# Main.net
KiCad netlist of a schematic drawn in Altium Designer
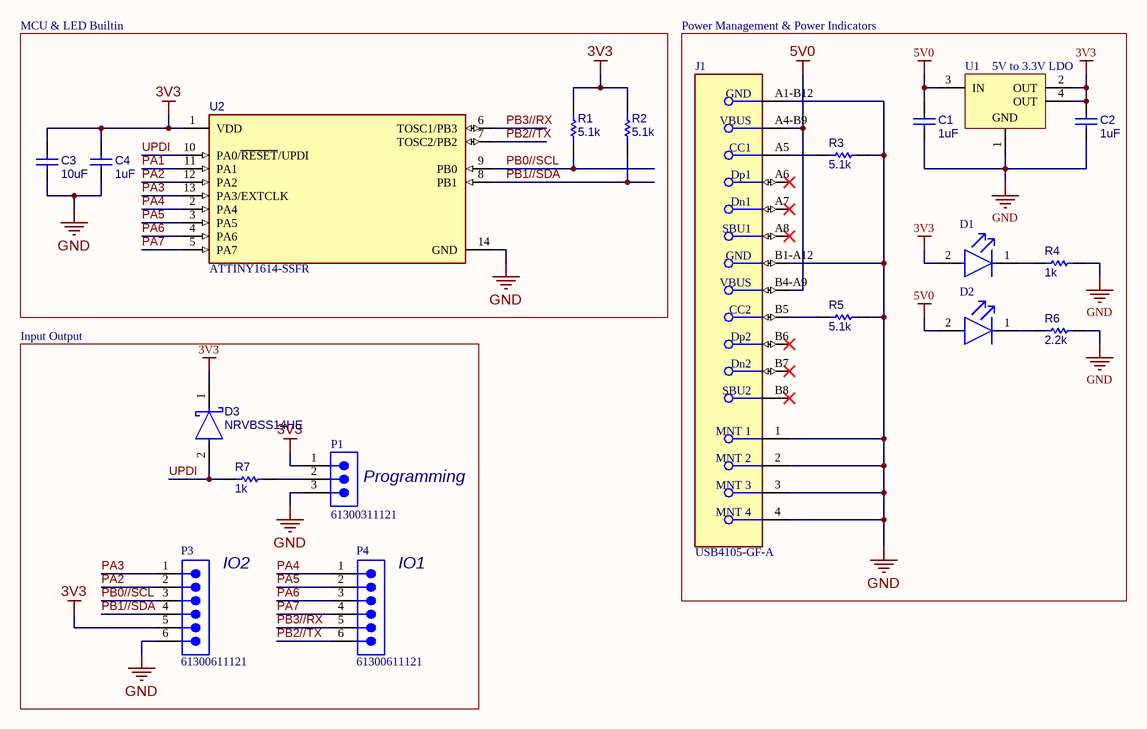
[diagram p0: Main.SchDoc]

(export (version "E")
  (design (tool "Eeschema 10.0.6"))
  (components
    (comp (ref "C1")
      (value "1uF")
      (footprint "WCAP-CSGP_0603_L1.6W0.8H0.8_Reflow")
      (description "10V tolerance")
      (libsource (lib "Altium Content Vault") (part "Capacitor_Non-Polarized"))
    )
    (comp (ref "C2")
      (value "1uF")
      (footprint "WCAP-CSGP_0603_L1.6W0.8H0.8_Reflow")
      (description "10V tolerance")
      (libsource (lib "Altium Content Vault") (part "Capacitor_Non-Polarized"))
    )
    (comp (ref "C3")
      (value "10uF")
      (footprint "WCAP-CSGP_0603_L1.6W0.8H0.8_Reflow")
      (description "10V tolerance")
      (libsource (lib "Altium Content Vault") (part "Capacitor_Non-Polarized"))
    )
    (comp (ref "C4")
      (value "1uF")
      (footprint "WCAP-CSGP_0603_L1.6W0.8H0.8_Reflow")
      (description "10V tolerance")
      (libsource (lib "Altium Content Vault") (part "Capacitor_Non-Polarized"))
    )
    (comp (ref "D1")
      (value "LTST-C190KGKT")
      (footprint "FP-LTST-C190KGKT-MFG")
      (description "LED GREEN CLEAR CHIP SMD")
      (libsource (lib "Altium Content Vault") (part "8706943c75ba83719d021d2fdc84c58"))
    )
    (comp (ref "D2")
      (value "LTST-C190KGKT")
      (footprint "FP-LTST-C190KGKT-MFG")
      (description "LED GREEN CLEAR CHIP SMD")
      (libsource (lib "Altium Content Vault") (part "8706943c75ba83719d021d2fdc84c58"))
    )
    (comp (ref "D3")
      (value "NRVBSS14HE")
      (footprint "FP-477AD-MFG")
      (description "NRVBSS14HE Rectifier Diode, Schottky, 1 Phase, 1 Element, 1A, 40V V(RRM), Silicon")
      (libsource (lib "Altium Content Vault") (part "c1678fac7984e62e0809fbf79c06691"))
    )
    (comp (ref "J1")
      (value "USB4105-GF-A")
      (footprint "FP-USB4105-GF-A-MFG")
      (description "CONN RCPT USB2.0 TYPEC 5A")
      (fields
        (field (name "MANUFACTURER") "GCT")
        (field (name "OCTOPART") "https://octopart.com/usb4105-gf-a-gct-106627878")
      )
      (libsource (lib "Altium Content Vault") (part "e7c17a616881a82b79941196b4bec10"))
    )
    (comp (ref "P1")
      (value "61300311121")
      (footprint "61300311121")
      (description "THT Vertical Pin Header WR-PHD, Pitch 2.54 mm, Single Row, 3 pins")
      (libsource (lib "Altium Content Vault") (part "Header_Male_1R_03P"))
    )
    (comp (ref "P3")
      (value "61300611121")
      (footprint "61300611121")
      (libsource (lib "Altium Content Vault") (part "Header_Male_1R_06P"))
    )
    (comp (ref "P4")
      (value "61300611121")
      (footprint "61300611121")
      (libsource (lib "Altium Content Vault") (part "Header_Male_1R_06P"))
    )
    (comp (ref "R1")
      (value "5.1k")
      (footprint "RESC1608X55X25NL10T15")
      (libsource (lib "Altium Content Vault") (part "RES"))
    )
    (comp (ref "R2")
      (value "5.1k")
      (footprint "RESC1608X55X25NL10T15")
      (libsource (lib "Altium Content Vault") (part "RES"))
    )
    (comp (ref "R3")
      (value "5.1k")
      (footprint "RESC1608X55X25NL10T15")
      (libsource (lib "Altium Content Vault") (part "RES"))
    )
    (comp (ref "R4")
      (value "1k")
      (footprint "RESC1608X55X25NL10T15")
      (libsource (lib "Altium Content Vault") (part "RES"))
    )
    (comp (ref "R5")
      (value "5.1k")
      (footprint "RESC1608X55X25NL10T15")
      (libsource (lib "Altium Content Vault") (part "RES"))
    )
    (comp (ref "R6")
      (value "2.2k")
      (footprint "RESC1608X55X25NL10T15")
      (libsource (lib "Altium Content Vault") (part "RES"))
    )
    (comp (ref "R7")
      (value "1k")
      (footprint "RESC1608X55X25NL10T15")
      (libsource (lib "Altium Content Vault") (part "RES"))
    )
    (comp (ref "U1")
      (value "TLV1117LV33DCYR")
      (footprint "DCY0004A_N")
      (fields (field (name "MANUFACTURER") "Texas Instruments"))
      (libsource (lib "Altium Content Vault") (part "TI-TLV1117LV33DCY4"))
    )
    (comp (ref "U2")
      (value "ATTINY1614-SSFR")
      (footprint "FP-C04-065-D3X-MFG")
      (description "IC MCU 8BIT 16KB FLASH 14SOIC")
      (fields
        (field (name "MANUFACTURER") "Microchip")
        (field (name "OCTOPART") "https://octopart.com/attiny1614-ssfr-microchip-82181131")
      )
      (libsource (lib "Altium Content Vault") (part "72c199063961b341655dca604db29b7"))
    )
  )
  (nets
    (net (code "1") (name "/PA1") (class "Default")
      (node (ref "U2") (pin "11") (pinfunction "PA1_11") (pintype "input"))
    )
    (net (code "2") (name "/PA2") (class "Default")
      (node (ref "P3") (pin "2") (pinfunction "2_2") (pintype "passive"))
      (node (ref "U2") (pin "12") (pinfunction "PA2_12") (pintype "input"))
    )
    (net (code "3") (name "/PA3") (class "Default")
      (node (ref "P3") (pin "1") (pinfunction "1_1") (pintype "passive"))
      (node (ref "U2") (pin "13") (pinfunction "PA3/EXTCLK_13") (pintype "input"))
    )
    (net (code "4") (name "/PA4") (class "Default")
      (node (ref "P4") (pin "1") (pinfunction "1_1") (pintype "passive"))
      (node (ref "U2") (pin "2") (pinfunction "PA4_2") (pintype "input"))
    )
    (net (code "5") (name "/PA5") (class "Default")
      (node (ref "P4") (pin "2") (pinfunction "2_2") (pintype "passive"))
      (node (ref "U2") (pin "3") (pinfunction "PA5_3") (pintype "input"))
    )
    (net (code "6") (name "/PA6") (class "Default")
      (node (ref "P4") (pin "3") (pinfunction "3_3") (pintype "passive"))
      (node (ref "U2") (pin "4") (pinfunction "PA6_4") (pintype "input"))
    )
    (net (code "7") (name "/PA7") (class "Default")
      (node (ref "P4") (pin "4") (pinfunction "4_4") (pintype "passive"))
      (node (ref "U2") (pin "5") (pinfunction "PA7_5") (pintype "input"))
    )
    (net (code "8") (name "/PB0{slash}{slash}SCL") (class "Default")
      (node (ref "P3") (pin "3") (pinfunction "3_3") (pintype "passive"))
      (node (ref "R1") (pin "2") (pinfunction "2_2") (pintype "passive"))
      (node (ref "U2") (pin "9") (pinfunction "PB0_9") (pintype "input"))
    )
    (net (code "9") (name "/PB1{slash}{slash}SDA") (class "Default")
      (node (ref "P3") (pin "4") (pinfunction "4_4") (pintype "passive"))
      (node (ref "R2") (pin "2") (pinfunction "2_2") (pintype "passive"))
      (node (ref "U2") (pin "8") (pinfunction "PB1_8") (pintype "input"))
    )
    (net (code "10") (name "/PB2{slash}{slash}TX") (class "Default")
      (node (ref "P4") (pin "6") (pinfunction "6_6") (pintype "passive"))
      (node (ref "U2") (pin "7") (pinfunction "TOSC2/PB2_7") (pintype "bidirectional"))
    )
    (net (code "11") (name "/PB3{slash}{slash}RX") (class "Default")
      (node (ref "P4") (pin "5") (pinfunction "5_5") (pintype "passive"))
      (node (ref "U2") (pin "6") (pinfunction "TOSC1/PB3_6") (pintype "bidirectional"))
    )
    (net (code "12") (name "/UPDI") (class "Default")
      (node (ref "D3") (pin "2") (pinfunction "A_2") (pintype "passive"))
      (node (ref "R7") (pin "1") (pinfunction "1_1") (pintype "passive"))
      (node (ref "U2") (pin "10") (pinfunction "PA0/~{RESET}/UPDI_10") (pintype "input"))
    )
    (net (code "13") (name "3V3") (class "Default")
      (node (ref "C2") (pin "2") (pinfunction "2_2") (pintype "passive"))
      (node (ref "C3") (pin "2") (pinfunction "2_2") (pintype "passive"))
      (node (ref "C4") (pin "2") (pinfunction "2_2") (pintype "passive"))
      (node (ref "D1") (pin "2") (pinfunction "A_2") (pintype "passive"))
      (node (ref "D3") (pin "1") (pinfunction "C_1") (pintype "passive"))
      (node (ref "P1") (pin "1") (pinfunction "1_1") (pintype "passive"))
      (node (ref "P3") (pin "5") (pinfunction "5_5") (pintype "passive"))
      (node (ref "R1") (pin "1") (pinfunction "1_1") (pintype "passive"))
      (node (ref "R2") (pin "1") (pinfunction "1_1") (pintype "passive"))
      (node (ref "U1") (pin "2") (pinfunction "OUT_2") (pintype "power_in"))
      (node (ref "U1") (pin "4") (pinfunction "OUT_4") (pintype "power_in"))
      (node (ref "U2") (pin "1") (pinfunction "VDD_1") (pintype "power_in"))
    )
    (net (code "14") (name "5V0") (class "Default")
      (node (ref "C1") (pin "2") (pinfunction "2_2") (pintype "passive"))
      (node (ref "D2") (pin "2") (pinfunction "A_2") (pintype "passive"))
      (node (ref "J1") (pin "A4-B9") (pinfunction "VBUS_A4-B9") (pintype "power_in"))
      (node (ref "J1") (pin "B4-A9") (pinfunction "VBUS_B4-A9") (pintype "bidirectional"))
      (node (ref "U1") (pin "3") (pinfunction "IN_3") (pintype "power_in"))
    )
    (net (code "15") (name "GND") (class "Default")
      (node (ref "C1") (pin "1") (pinfunction "1_1") (pintype "passive"))
      (node (ref "C2") (pin "1") (pinfunction "1_1") (pintype "passive"))
      (node (ref "C3") (pin "1") (pinfunction "1_1") (pintype "passive"))
      (node (ref "C4") (pin "1") (pinfunction "1_1") (pintype "passive"))
      (node (ref "J1") (pin "1") (pinfunction "MNT_1_1") (pintype "power_in"))
      (node (ref "J1") (pin "2") (pinfunction "MNT_2_2") (pintype "power_in"))
      (node (ref "J1") (pin "3") (pinfunction "MNT_3_3") (pintype "power_in"))
      (node (ref "J1") (pin "4") (pinfunction "MNT_4_4") (pintype "power_in"))
      (node (ref "J1") (pin "A1-B12") (pinfunction "GND_A1-B12") (pintype "power_in"))
      (node (ref "J1") (pin "B1-A12") (pinfunction "GND_B1-A12") (pintype "bidirectional"))
      (node (ref "P1") (pin "3") (pinfunction "3_3") (pintype "passive"))
      (node (ref "P3") (pin "6") (pinfunction "6_6") (pintype "passive"))
      (node (ref "R3") (pin "2") (pinfunction "2_2") (pintype "passive"))
      (node (ref "R4") (pin "2") (pinfunction "2_2") (pintype "passive"))
      (node (ref "R5") (pin "2") (pinfunction "2_2") (pintype "passive"))
      (node (ref "R6") (pin "2") (pinfunction "2_2") (pintype "passive"))
      (node (ref "U1") (pin "1") (pinfunction "GND_1") (pintype "power_in"))
      (node (ref "U2") (pin "14") (pinfunction "GND_14") (pintype "power_in"))
    )
    (net (code "16") (name "Net-(D1-C)") (class "Default")
      (node (ref "D1") (pin "1") (pinfunction "C_1") (pintype "passive"))
      (node (ref "R4") (pin "1") (pinfunction "1_1") (pintype "passive"))
    )
    (net (code "17") (name "Net-(D2-C)") (class "Default")
      (node (ref "D2") (pin "1") (pinfunction "C_1") (pintype "passive"))
      (node (ref "R6") (pin "1") (pinfunction "1_1") (pintype "passive"))
    )
    (net (code "18") (name "Net-(J1-CC1)") (class "Default")
      (node (ref "J1") (pin "A5") (pinfunction "CC1_A5") (pintype "power_in"))
      (node (ref "R3") (pin "1") (pinfunction "1_1") (pintype "passive"))
    )
    (net (code "19") (name "Net-(J1-CC2)") (class "Default")
      (node (ref "J1") (pin "B5") (pinfunction "CC2_B5") (pintype "bidirectional"))
      (node (ref "R5") (pin "1") (pinfunction "1_1") (pintype "passive"))
    )
    (net (code "20") (name "Net-(P1-Pad2)") (class "Default")
      (node (ref "P1") (pin "2") (pinfunction "2_2") (pintype "passive"))
      (node (ref "R7") (pin "2") (pinfunction "2_2") (pintype "passive"))
    )
    (net (code "21") (name "unconnected-(J1-Dn1-PadA7)") (class "Default")
      (node (ref "J1") (pin "A7") (pinfunction "Dn1_A7") (pintype "bidirectional+no_connect"))
    )
    (net (code "22") (name "unconnected-(J1-Dn2-PadB7)") (class "Default")
      (node (ref "J1") (pin "B7") (pinfunction "Dn2_B7") (pintype "bidirectional+no_connect"))
    )
    (net (code "23") (name "unconnected-(J1-Dp1-PadA6)") (class "Default")
      (node (ref "J1") (pin "A6") (pinfunction "Dp1_A6") (pintype "bidirectional+no_connect"))
    )
    (net (code "24") (name "unconnected-(J1-Dp2-PadB6)") (class "Default")
      (node (ref "J1") (pin "B6") (pinfunction "Dp2_B6") (pintype "bidirectional+no_connect"))
    )
    (net (code "25") (name "unconnected-(J1-SBU1-PadA8)") (class "Default")
      (node (ref "J1") (pin "A8") (pinfunction "SBU1_A8") (pintype "bidirectional+no_connect"))
    )
    (net (code "26") (name "unconnected-(J1-SBU2-PadB8)") (class "Default")
      (node (ref "J1") (pin "B8") (pinfunction "SBU2_B8") (pintype "power_in+no_connect"))
    )
  )
)
